# STM32H730_PINOUT.net
KiCad netlist of a schematic drawn in Altium Designer
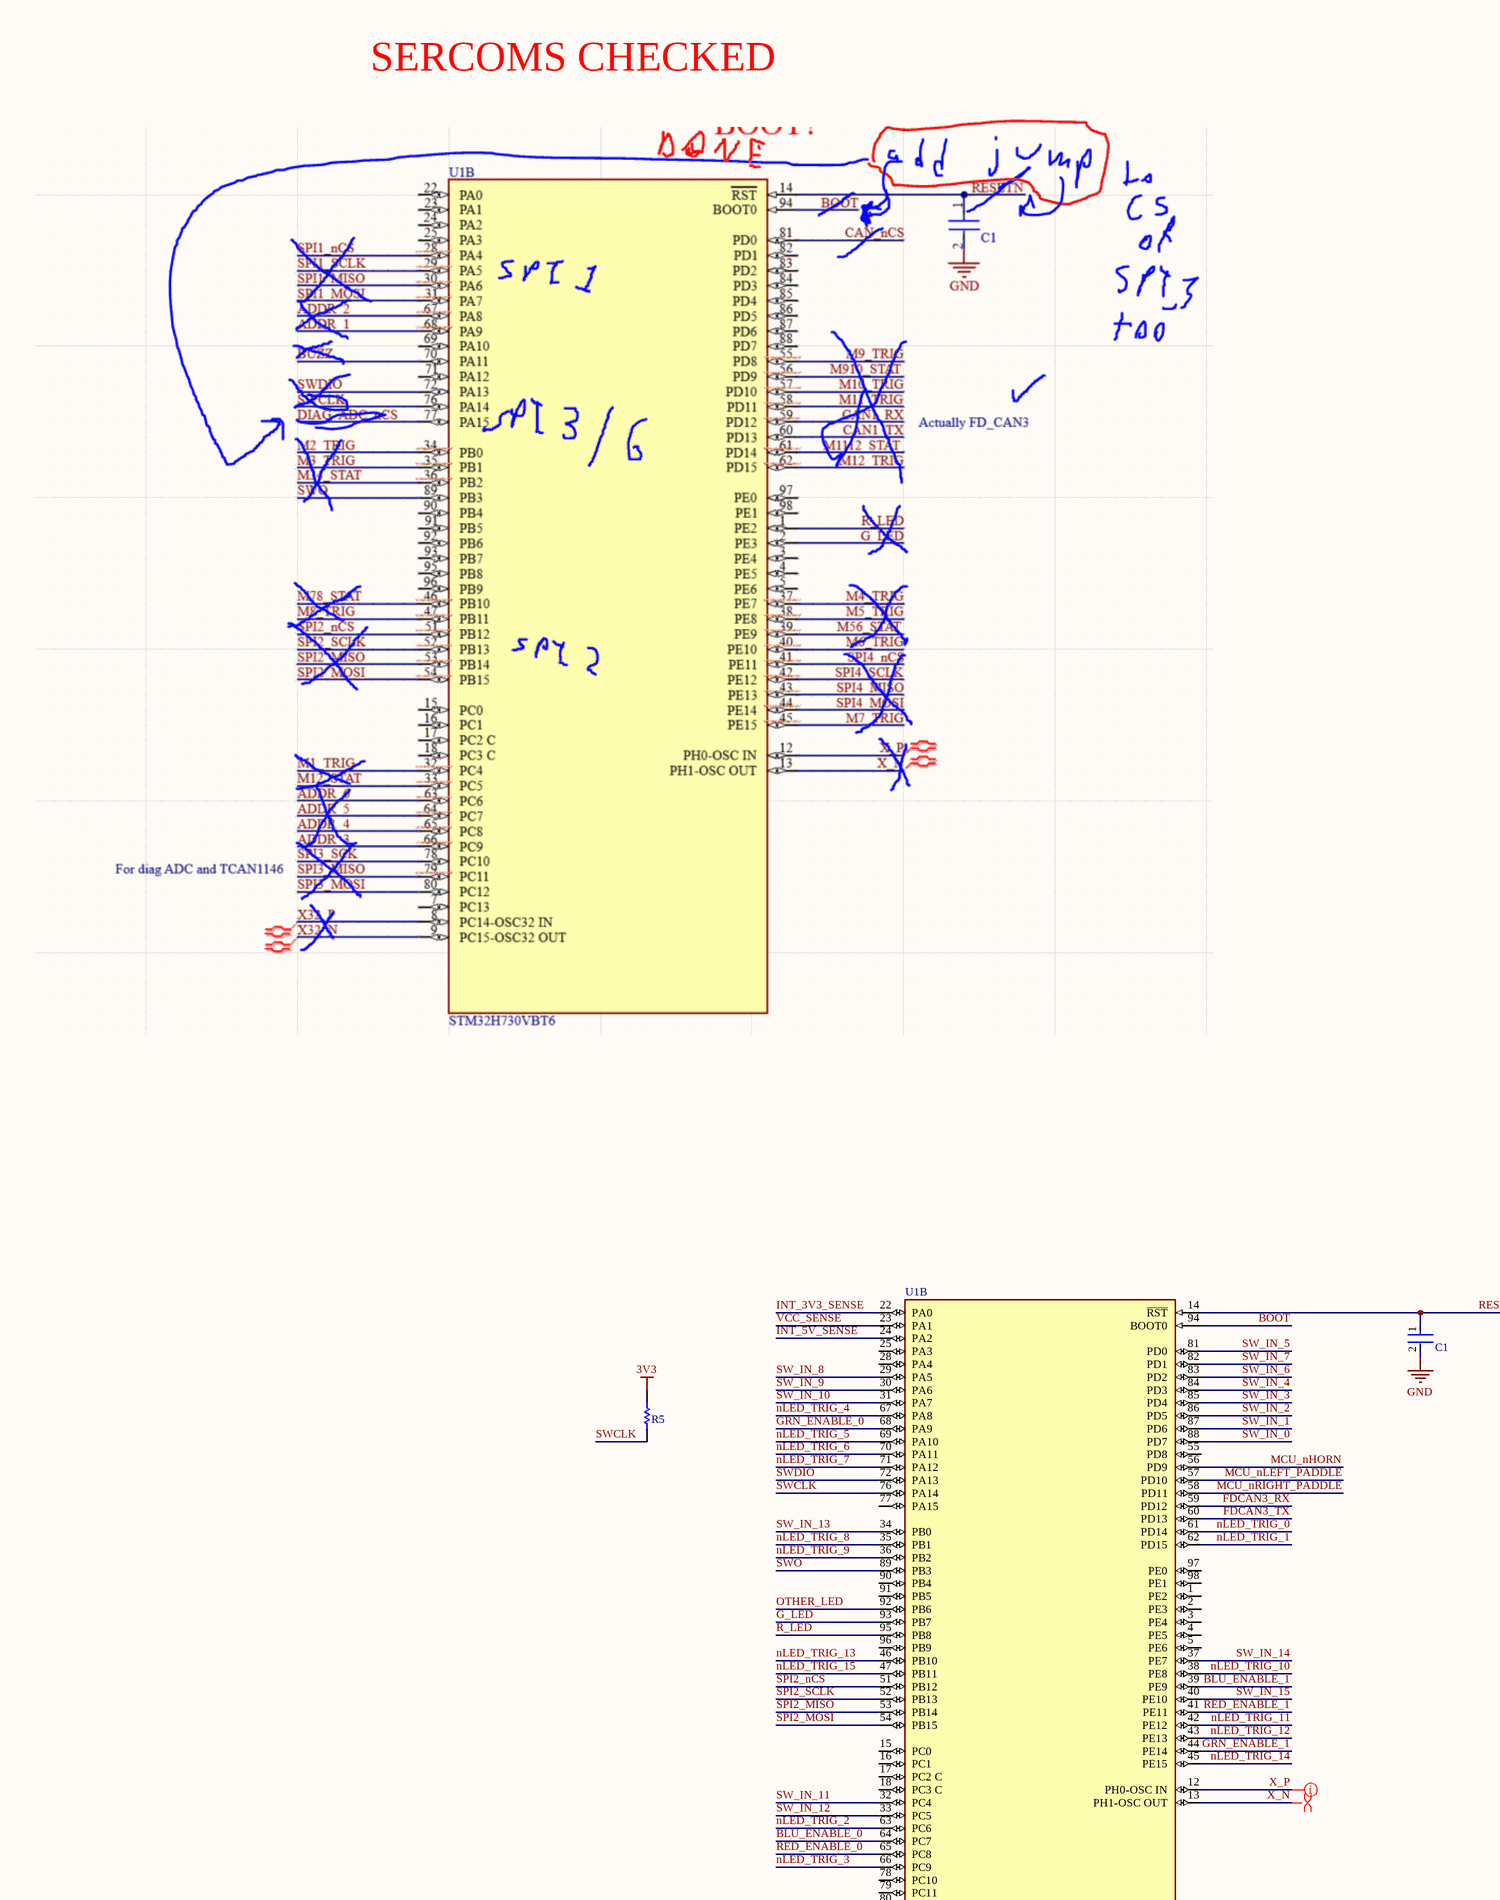
[diagram p0: STM32H730_PINOUT.SchDoc, top left]
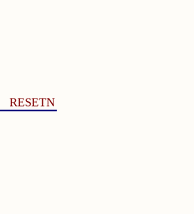
[diagram p1: STM32H730_PINOUT.SchDoc, top middle]
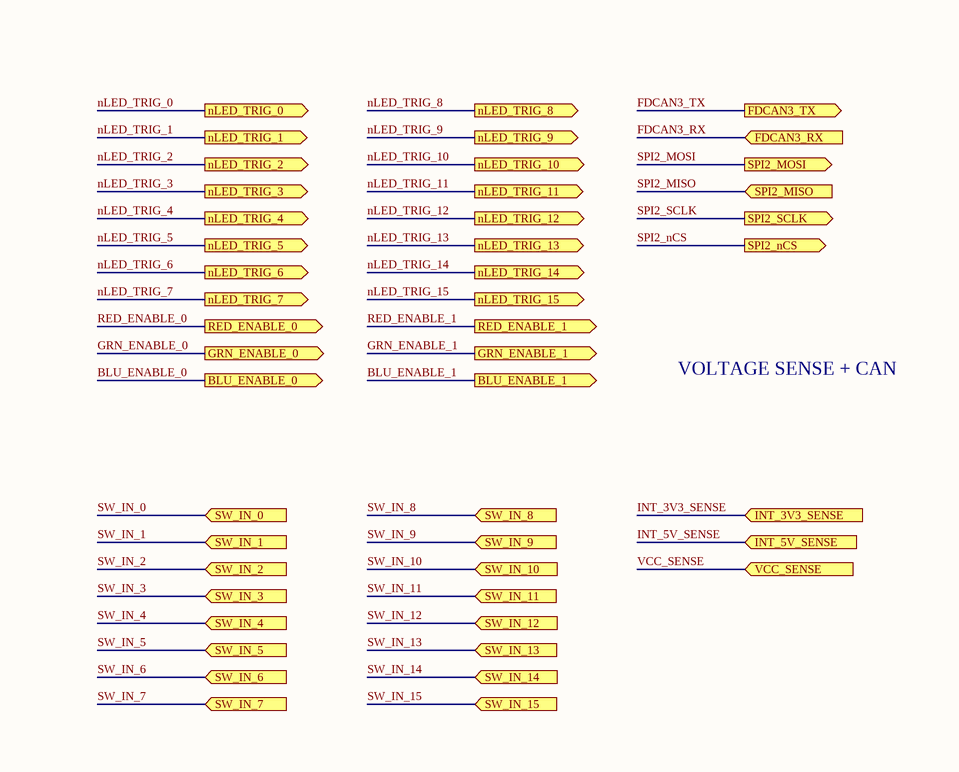
[diagram p2: STM32H730_PINOUT.SchDoc, top right]
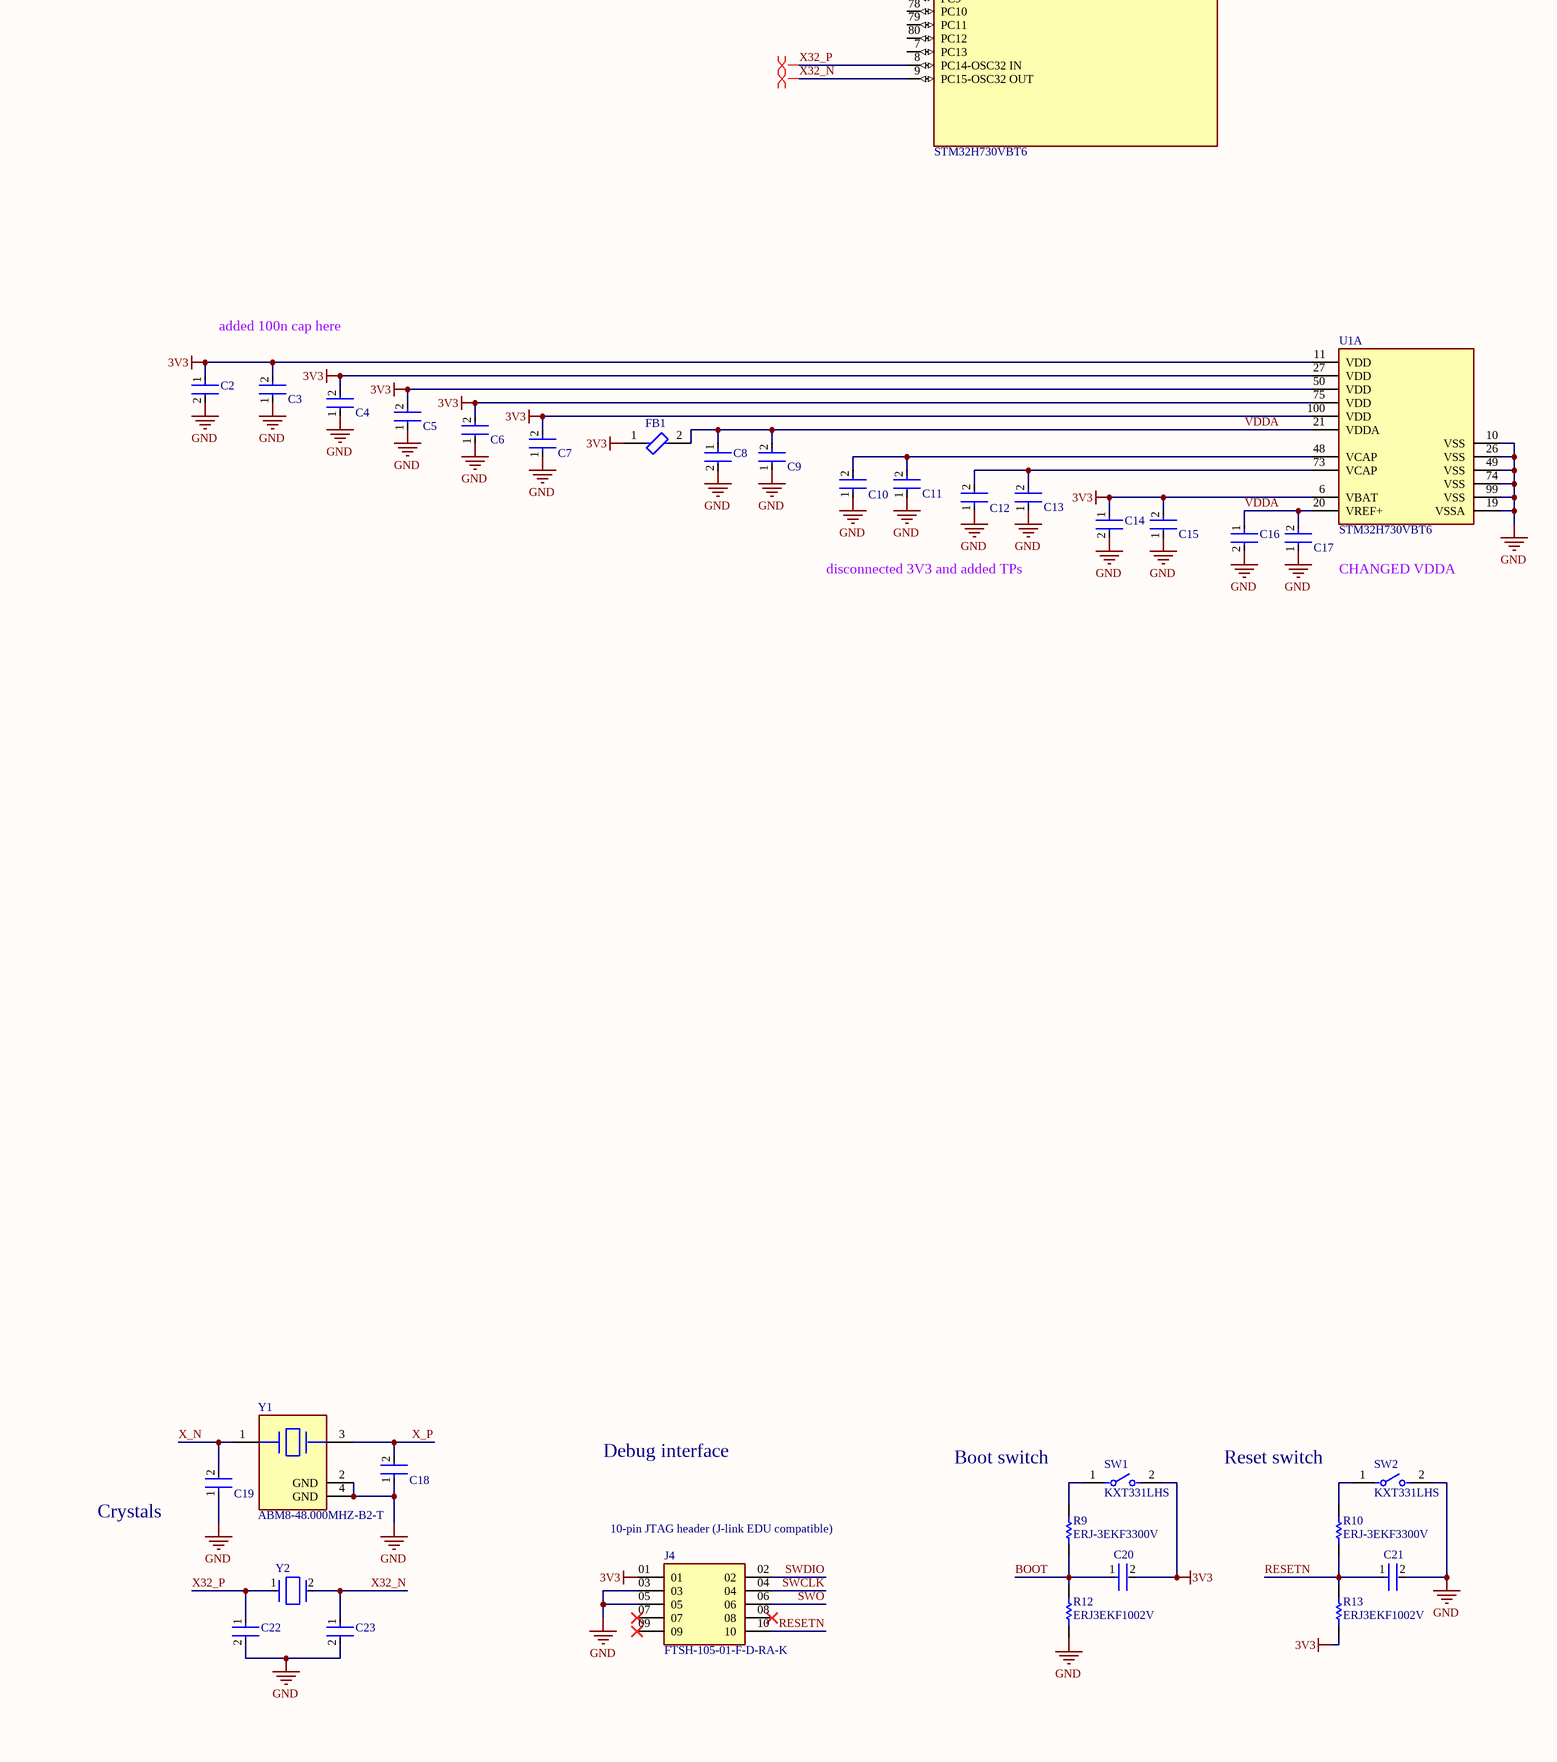
[diagram p3: STM32H730_PINOUT.SchDoc, bottom left]
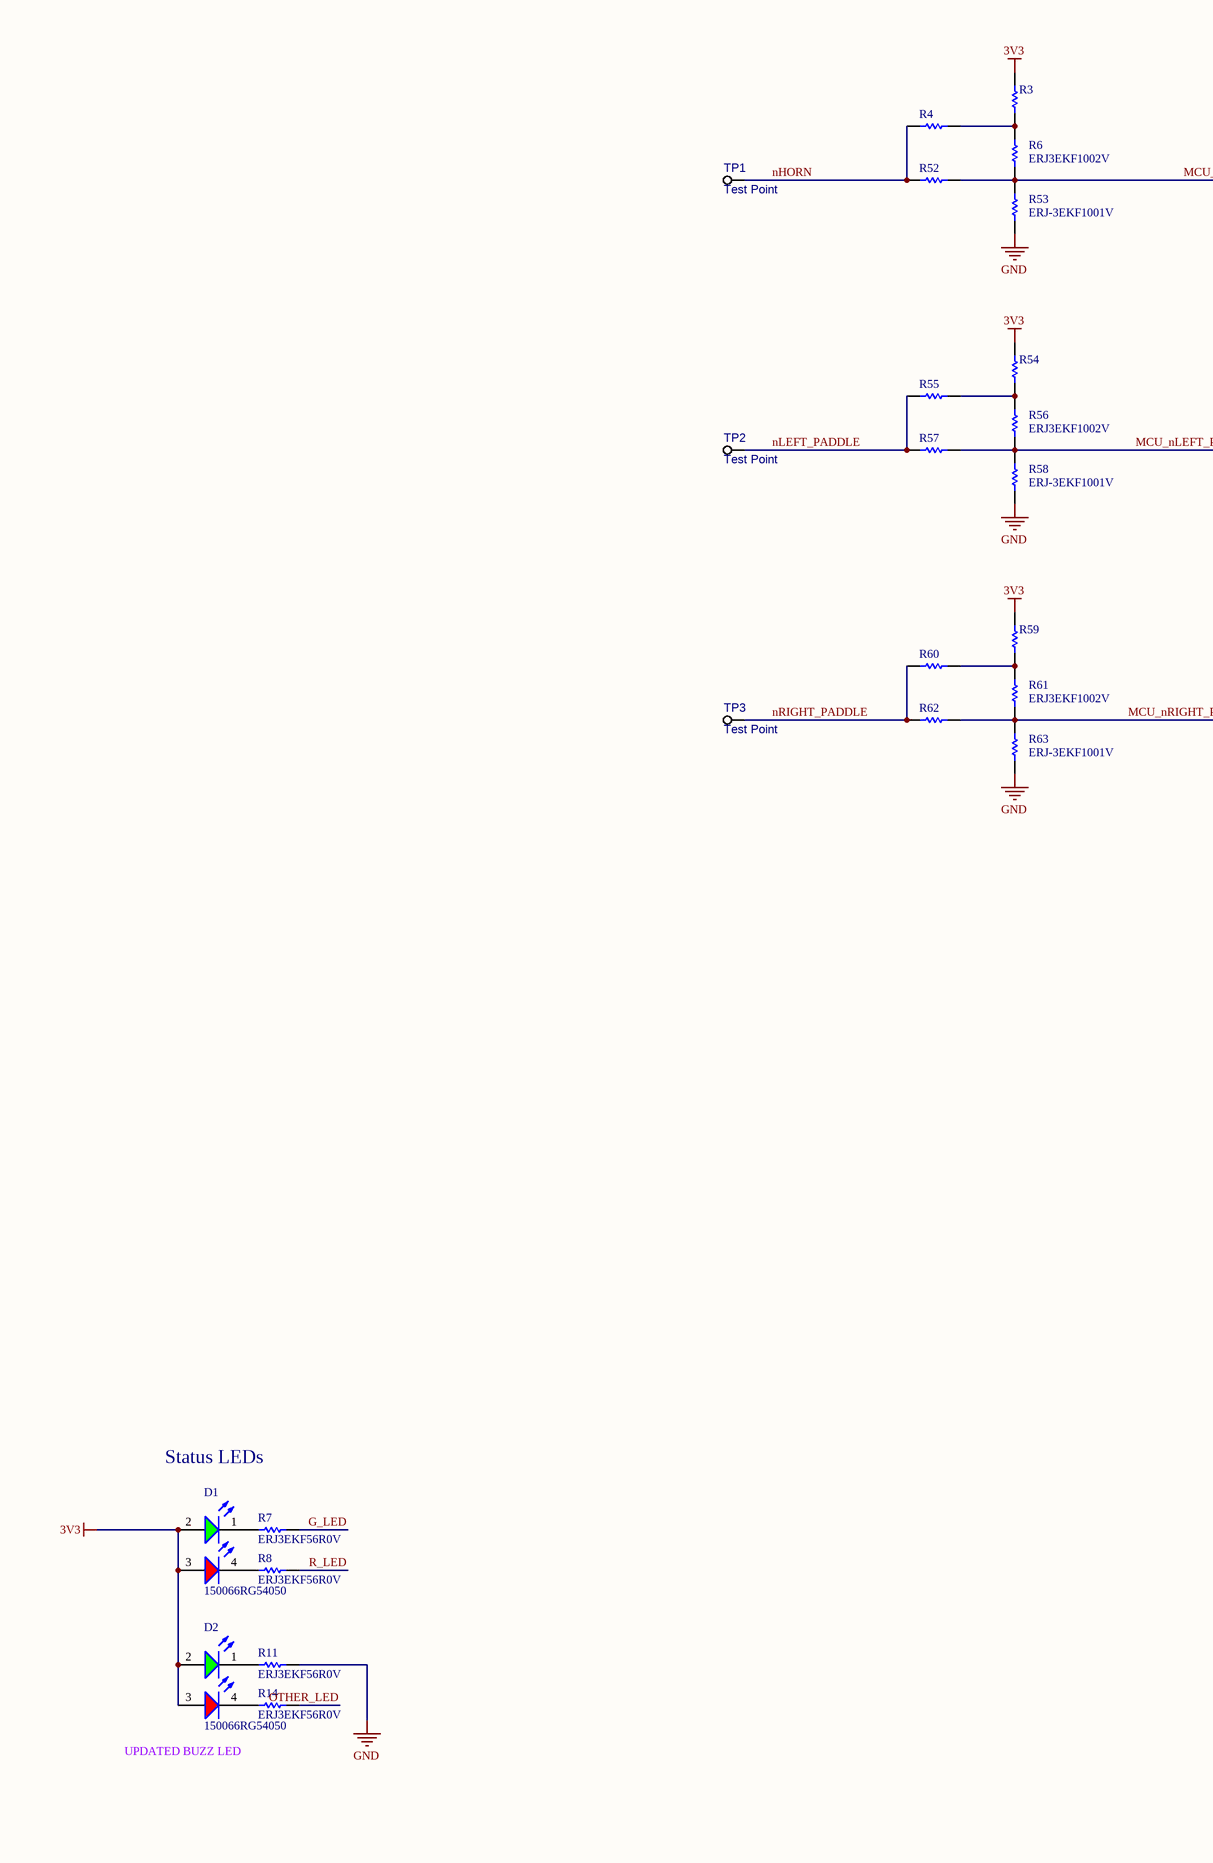
[diagram p4: STM32H730_PINOUT.SchDoc, bottom middle]
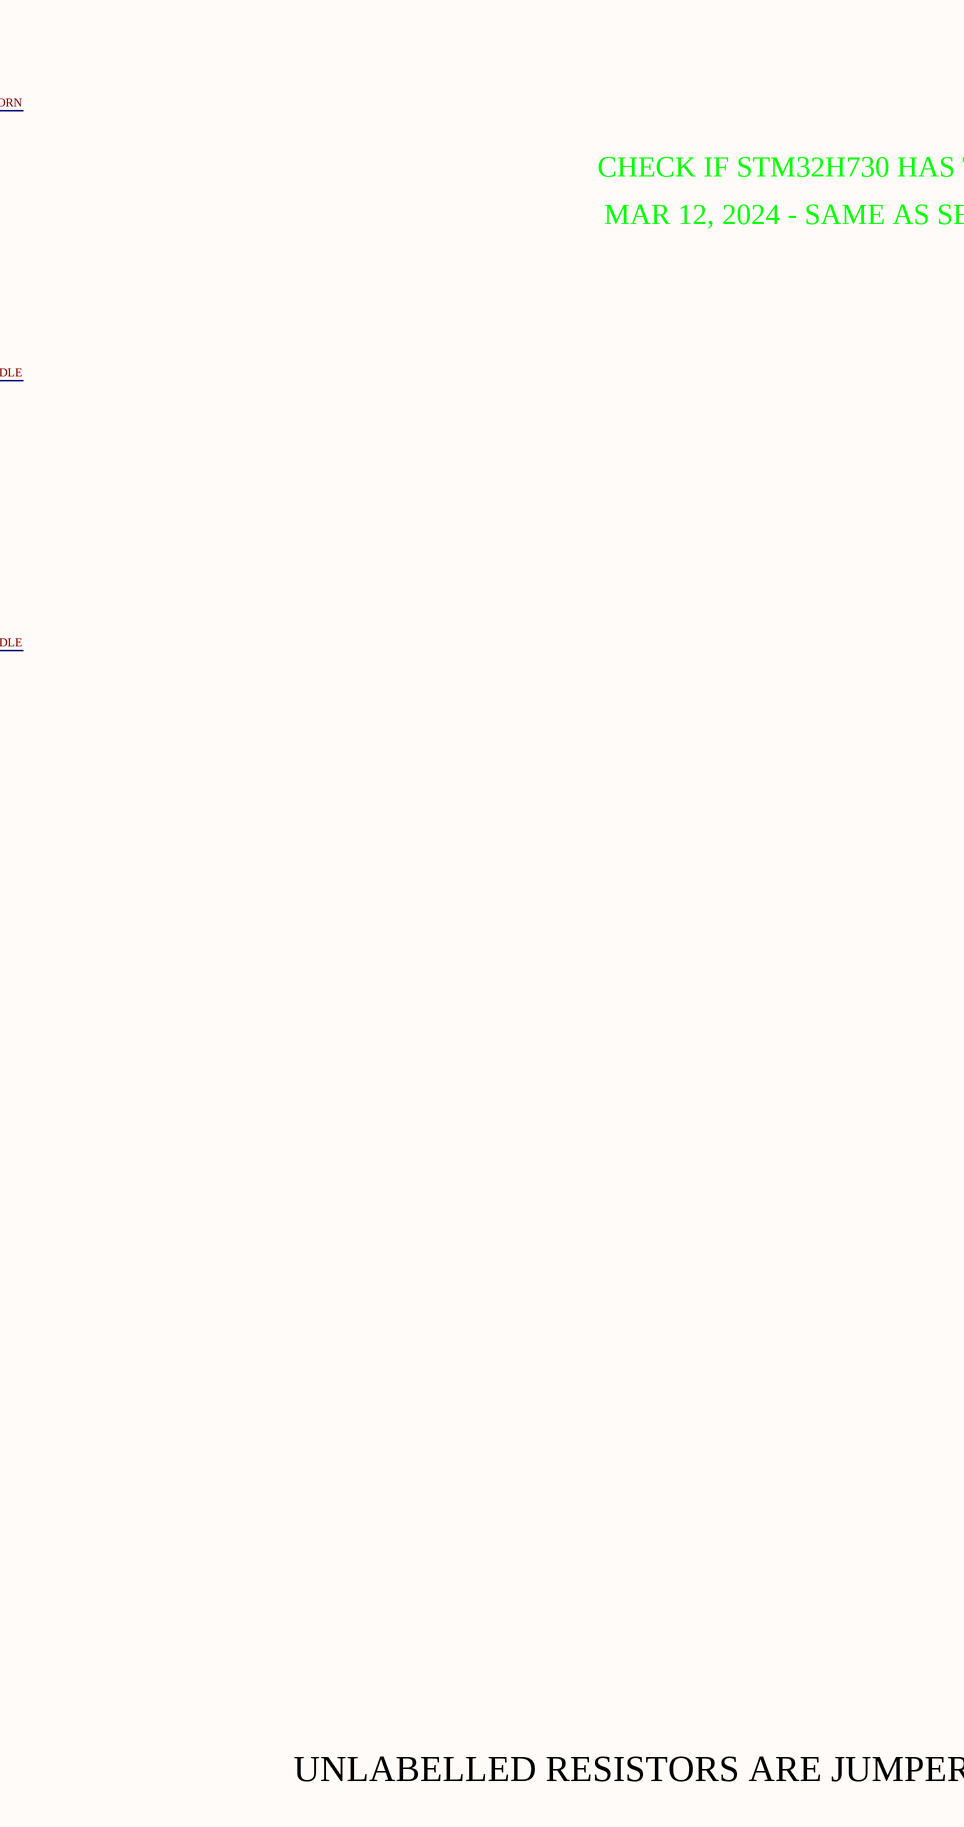
[diagram p5: STM32H730_PINOUT.SchDoc, bottom right]

(export (version "E")
  (design (tool "Eeschema 10.0.6"))
  (components
    (comp (ref "C1")
      (value "C0402C104K8PACTU")
      (footprint "FP-C0402-BB-MFG")
      (description "CAP CER 0.1UF 10V X5R 0402")
      (fields (field (name "MANUFACTURER") "Kemet") (field (name "TOLERANCE") "0.1"))
      (libsource (lib "Altium Content Vault") (part "b4654b650e69147ec39a6b967a45e02"))
    )
    (comp (ref "C2")
      (value "C1005X5R1A475K050BC")
      (footprint "FP-C1005-050-0_15-MFG")
      (description "CAP CER 4.7UF 10V X5R 0402")
      (fields (field (name "TOLERANCE") "10%"))
      (libsource (lib "Altium Content Vault") (part "b4654b650e69147ec39a6b967a45e02"))
    )
    (comp (ref "C3")
      (value "GRM155R71C104KA88D")
      (footprint "FP-GRM15-MFG")
      (description "CAP CER 0.1UF 16V X7R 0402")
      (fields
        (field (name "TOLERANCE") "10%")
        (field (name "OCTOPART") "https://octopart.com/grm155r71c104ka88d-murata-196880")
      )
      (libsource (lib "Altium Content Vault") (part "236180d848d6139a670b325ea6854c9"))
    )
    (comp (ref "C4")
      (value "GRM155R71C104KA88D")
      (footprint "FP-GRM15-MFG")
      (description "CAP CER 0.1UF 16V X7R 0402")
      (fields
        (field (name "TOLERANCE") "10%")
        (field (name "OCTOPART") "https://octopart.com/grm155r71c104ka88d-murata-196880")
      )
      (libsource (lib "Altium Content Vault") (part "236180d848d6139a670b325ea6854c9"))
    )
    (comp (ref "C5")
      (value "GRM155R71C104KA88D")
      (footprint "FP-GRM15-MFG")
      (description "CAP CER 0.1UF 16V X7R 0402")
      (fields
        (field (name "TOLERANCE") "10%")
        (field (name "OCTOPART") "https://octopart.com/grm155r71c104ka88d-murata-196880")
      )
      (libsource (lib "Altium Content Vault") (part "236180d848d6139a670b325ea6854c9"))
    )
    (comp (ref "C6")
      (value "GRM155R71C104KA88D")
      (footprint "FP-GRM15-MFG")
      (description "CAP CER 0.1UF 16V X7R 0402")
      (fields
        (field (name "TOLERANCE") "10%")
        (field (name "OCTOPART") "https://octopart.com/grm155r71c104ka88d-murata-196880")
      )
      (libsource (lib "Altium Content Vault") (part "236180d848d6139a670b325ea6854c9"))
    )
    (comp (ref "C7")
      (value "GRM155R71C104KA88D")
      (footprint "FP-GRM15-MFG")
      (description "CAP CER 0.1UF 16V X7R 0402")
      (fields
        (field (name "TOLERANCE") "10%")
        (field (name "OCTOPART") "https://octopart.com/grm155r71c104ka88d-murata-196880")
      )
      (libsource (lib "Altium Content Vault") (part "236180d848d6139a670b325ea6854c9"))
    )
    (comp (ref "C8")
      (value "EMK105BJ105KV-F")
      (footprint "FP-0402-L_1_0_0_05-W_0_5-IPC_A")
      (description "None")
      (fields (field (name "TOLERANCE") "10%"))
      (libsource (lib "Altium Content Vault") (part "b4654b650e69147ec39a6b967a45e02"))
    )
    (comp (ref "C9")
      (value "GRM155R71C104KA88D")
      (footprint "FP-GRM15-MFG")
      (description "CAP CER 0.1UF 16V X7R 0402")
      (fields
        (field (name "TOLERANCE") "10%")
        (field (name "OCTOPART") "https://octopart.com/grm155r71c104ka88d-murata-196880")
      )
      (libsource (lib "Altium Content Vault") (part "236180d848d6139a670b325ea6854c9"))
    )
    (comp (ref "C10")
      (value "C1005X7S1A225K050BC")
      (footprint "FP-C1005-050-0_15-0_1-MFG")
      (description "CAP CER 2.2UF 10V X7S 0402")
      (fields (field (name "TOLERANCE") "10%"))
      (libsource (lib "Altium Content Vault") (part "b4654b650e69147ec39a6b967a45e02"))
    )
    (comp (ref "C11")
      (value "GRM155R71C104KA88D")
      (footprint "FP-GRM15-MFG")
      (description "CAP CER 0.1UF 16V X7R 0402")
      (fields
        (field (name "TOLERANCE") "10%")
        (field (name "OCTOPART") "https://octopart.com/grm155r71c104ka88d-murata-196880")
      )
      (libsource (lib "Altium Content Vault") (part "236180d848d6139a670b325ea6854c9"))
    )
    (comp (ref "C12")
      (value "C1005X7S1A225K050BC")
      (footprint "FP-C1005-050-0_15-0_1-MFG")
      (description "CAP CER 2.2UF 10V X7S 0402")
      (fields (field (name "TOLERANCE") "10%"))
      (libsource (lib "Altium Content Vault") (part "b4654b650e69147ec39a6b967a45e02"))
    )
    (comp (ref "C13")
      (value "GRM155R71C104KA88D")
      (footprint "FP-GRM15-MFG")
      (description "CAP CER 0.1UF 16V X7R 0402")
      (fields
        (field (name "TOLERANCE") "10%")
        (field (name "OCTOPART") "https://octopart.com/grm155r71c104ka88d-murata-196880")
      )
      (libsource (lib "Altium Content Vault") (part "236180d848d6139a670b325ea6854c9"))
    )
    (comp (ref "C14")
      (value "EMK105BJ105KV-F")
      (footprint "FP-0402-L_1_0_0_05-W_0_5-IPC_A")
      (description "None")
      (fields (field (name "TOLERANCE") "10%"))
      (libsource (lib "Altium Content Vault") (part "b4654b650e69147ec39a6b967a45e02"))
    )
    (comp (ref "C15")
      (value "GRM155R71C104KA88D")
      (footprint "FP-GRM15-MFG")
      (description "CAP CER 0.1UF 16V X7R 0402")
      (fields
        (field (name "TOLERANCE") "10%")
        (field (name "OCTOPART") "https://octopart.com/grm155r71c104ka88d-murata-196880")
      )
      (libsource (lib "Altium Content Vault") (part "236180d848d6139a670b325ea6854c9"))
    )
    (comp (ref "C16")
      (value "EMK105BJ105KV-F")
      (footprint "FP-0402-L_1_0_0_05-W_0_5-IPC_A")
      (description "None")
      (fields (field (name "TOLERANCE") "10%"))
      (libsource (lib "Altium Content Vault") (part "b4654b650e69147ec39a6b967a45e02"))
    )
    (comp (ref "C17")
      (value "GRM155R71C104KA88D")
      (footprint "FP-GRM15-MFG")
      (description "CAP CER 0.1UF 16V X7R 0402")
      (fields
        (field (name "TOLERANCE") "10%")
        (field (name "OCTOPART") "https://octopart.com/grm155r71c104ka88d-murata-196880")
      )
      (libsource (lib "Altium Content Vault") (part "236180d848d6139a670b325ea6854c9"))
    )
    (comp (ref "C18")
      (value "08051A6R8CAT2A")
      (footprint "FP-0805-L_2_01_0_2-W_1_25-MFG")
      (description "General Purpose Ceramic Capacitor, 0805, 6.8pF, 0.25pF, C0G, 30ppm/°C, 100V")
      (fields (field (name "VOLTAGE") "100V") (field (name "TOLERANCE") "5%"))
      (libsource (lib "Altium Content Vault") (part "02cd4be3c70576c341d710602a673aa"))
    )
    (comp (ref "C19")
      (value "08051A6R8CAT2A")
      (footprint "FP-0805-L_2_01_0_2-W_1_25-MFG")
      (description "General Purpose Ceramic Capacitor, 0805, 6.8pF, 0.25pF, C0G, 30ppm/°C, 100V")
      (fields (field (name "VOLTAGE") "100V") (field (name "TOLERANCE") "5%"))
      (libsource (lib "Altium Content Vault") (part "02cd4be3c70576c341d710602a673aa"))
    )
    (comp (ref "C20")
      (value "C0402C104K8PACTU")
      (footprint "FP-C0402-BB-MFG")
      (description "CAP CER 0.1UF 10V X5R 0402")
      (fields (field (name "MANUFACTURER") "Kemet") (field (name "TOLERANCE") "0.1"))
      (libsource (lib "Altium Content Vault") (part "b4654b650e69147ec39a6b967a45e02"))
    )
    (comp (ref "C21")
      (value "C0402C104K8PACTU")
      (footprint "FP-C0402-BB-MFG")
      (description "CAP CER 0.1UF 10V X5R 0402")
      (fields (field (name "MANUFACTURER") "Kemet") (field (name "TOLERANCE") "0.1"))
      (libsource (lib "Altium Content Vault") (part "b4654b650e69147ec39a6b967a45e02"))
    )
    (comp (ref "C22")
      (value "04025A180FAT2A")
      (footprint "FP-0402-L_1_0_1-W_0_5_0_1-IPC_A")
      (description "General Purpose Ceramic Capacitor, 0402, 18pF, 1%, C0G, 30ppm/°C, 50V")
      (fields (field (name "TOLERANCE") "1%"))
      (libsource (lib "Altium Content Vault") (part "b4654b650e69147ec39a6b967a45e02"))
    )
    (comp (ref "C23")
      (value "04025A180FAT2A")
      (footprint "FP-0402-L_1_0_1-W_0_5_0_1-IPC_A")
      (description "General Purpose Ceramic Capacitor, 0402, 18pF, 1%, C0G, 30ppm/°C, 50V")
      (fields (field (name "TOLERANCE") "1%"))
      (libsource (lib "Altium Content Vault") (part "b4654b650e69147ec39a6b967a45e02"))
    )
    (comp (ref "D1")
      (value "150066RG54050")
      (footprint "WL-SBCD_0606")
      (description "Led, Red/Grn, 180Mcd/230Mcd, 624Nm/525Nm Rohs Compliant: Yes")
      (fields (field (name "SOURCE") "rgled.SchLib"))
      (libsource (lib "Space Concordia") (part "CMP-004-00034-2"))
    )
    (comp (ref "D2")
      (value "150066RG54050")
      (footprint "WL-SBCD_0606")
      (description "Led, Red/Grn, 180Mcd/230Mcd, 624Nm/525Nm Rohs Compliant: Yes")
      (fields (field (name "SOURCE") "rgled.SchLib"))
      (libsource (lib "Space Concordia") (part "CMP-004-00034-2"))
    )
    (comp (ref "FB1")
      (value "BLM15PX601SN1D")
      (footprint "FP-BLM15-0_05-MFG")
      (description "Chip Ferrite Bead, 0402, 600Ω @ 100MHz, 0.23Ω, 25%, 900mA")
      (fields (field (name "TOLERANCE") "25%"))
      (libsource (lib "Altium Content Vault") (part "5f30dd21d616792df468990f7003faa"))
    )
    (comp (ref "J4")
      (value "FTSH-105-01-F-D-RA-K")
      (footprint "FTSH-105-01-F-D-RA-K-Footprint-1")
      (libsource (lib "Space Concordia") (part "FTSH-105-01-F-D-RA-K-Symbol-1"))
    )
    (comp (ref "R3")
      (value "0402 JUMPER")
      (footprint "RESC1005X40X25ML05T05")
      (description "READ THE NAME")
      (libsource (lib "Space Concordia") (part "CMP-009-00206-2"))
    )
    (comp (ref "R4")
      (value "0402 JUMPER")
      (footprint "RESC1005X40X25ML05T05")
      (description "READ THE NAME")
      (libsource (lib "Space Concordia") (part "CMP-009-00206-2"))
    )
    (comp (ref "R5")
      (value "ERJ3EKF1002V")
      (footprint "RESC1609X55X30LL15T15")
      (description "Chip Resistor, 10 KOhm, +/- 1%, 0.1 W, -55 to 155 degC, 0603 (1608 Metric), RoHS, Tape and Reel")
      (fields (field (name "TOLERANCE") "1%") (field (name "MANUFACTURER") "Panasonic"))
      (libsource (lib "Altium Content Vault") (part "RES-2"))
    )
    (comp (ref "R6")
      (value "ERJ3EKF1002V")
      (footprint "RESC1609X55X30LL15T15")
      (description "Chip Resistor, 10 KOhm, +/- 1%, 0.1 W, -55 to 155 degC, 0603 (1608 Metric), RoHS, Tape and Reel")
      (fields (field (name "TOLERANCE") "1%") (field (name "MANUFACTURER") "Panasonic"))
      (libsource (lib "Altium Content Vault") (part "RES-2"))
    )
    (comp (ref "R7")
      (value "ERJ3EKF56R0V")
      (footprint "RESC1608X55X30NL15T15")
      (fields (field (name "MANUFACTURER") "Panasonic"))
      (libsource (lib "Altium Content Vault") (part "RES"))
    )
    (comp (ref "R8")
      (value "ERJ3EKF56R0V")
      (footprint "RESC1608X55X30NL15T15")
      (fields (field (name "MANUFACTURER") "Panasonic"))
      (libsource (lib "Altium Content Vault") (part "RES"))
    )
    (comp (ref "R9")
      (value "ERJ-3EKF3300V")
      (footprint "RESC1608X55X30LL15T15")
      (description "Chip Resistor, 330 Ohm, +/- 1%, 0.1 W, -55 to 155 degC, 0603 (1608 Metric), RoHS, Tape and Reel")
      (libsource (lib "Altium Content Vault") (part "RES-2"))
    )
    (comp (ref "R10")
      (value "ERJ-3EKF3300V")
      (footprint "RESC1608X55X30LL15T15")
      (description "Chip Resistor, 330 Ohm, +/- 1%, 0.1 W, -55 to 155 degC, 0603 (1608 Metric), RoHS, Tape and Reel")
      (libsource (lib "Altium Content Vault") (part "RES-2"))
    )
    (comp (ref "R11")
      (value "ERJ3EKF56R0V")
      (footprint "RESC1608X55X30NL15T15")
      (fields (field (name "MANUFACTURER") "Panasonic"))
      (libsource (lib "Altium Content Vault") (part "RES"))
    )
    (comp (ref "R12")
      (value "ERJ3EKF1002V")
      (footprint "RESC1609X55X30LL15T15")
      (description "Chip Resistor, 10 KOhm, +/- 1%, 0.1 W, -55 to 155 degC, 0603 (1608 Metric), RoHS, Tape and Reel")
      (fields (field (name "TOLERANCE") "1%") (field (name "MANUFACTURER") "Panasonic"))
      (libsource (lib "Altium Content Vault") (part "RES-2"))
    )
    (comp (ref "R13")
      (value "ERJ3EKF1002V")
      (footprint "RESC1609X55X30LL15T15")
      (description "Chip Resistor, 10 KOhm, +/- 1%, 0.1 W, -55 to 155 degC, 0603 (1608 Metric), RoHS, Tape and Reel")
      (fields (field (name "TOLERANCE") "1%") (field (name "MANUFACTURER") "Panasonic"))
      (libsource (lib "Altium Content Vault") (part "RES-2"))
    )
    (comp (ref "R14")
      (value "ERJ3EKF56R0V")
      (footprint "RESC1608X55X30NL15T15")
      (fields (field (name "MANUFACTURER") "Panasonic"))
      (libsource (lib "Altium Content Vault") (part "RES"))
    )
    (comp (ref "R52")
      (value "0402 JUMPER")
      (footprint "RESC1005X40X25ML05T05")
      (description "READ THE NAME")
      (libsource (lib "Space Concordia") (part "CMP-009-00206-2"))
    )
    (comp (ref "R53")
      (value "ERJ-3EKF1001V")
      (footprint "RESC1608X55X30LL15T15")
      (fields (field (name "MANUFACTURER") "Panasonic"))
      (libsource (lib "Altium Content Vault") (part "RES"))
    )
    (comp (ref "R54")
      (value "0402 JUMPER")
      (footprint "RESC1005X40X25ML05T05")
      (description "READ THE NAME")
      (libsource (lib "Space Concordia") (part "CMP-009-00206-2"))
    )
    (comp (ref "R55")
      (value "0402 JUMPER")
      (footprint "RESC1005X40X25ML05T05")
      (description "READ THE NAME")
      (libsource (lib "Space Concordia") (part "CMP-009-00206-2"))
    )
    (comp (ref "R56")
      (value "ERJ3EKF1002V")
      (footprint "RESC1609X55X30LL15T15")
      (description "Chip Resistor, 10 KOhm, +/- 1%, 0.1 W, -55 to 155 degC, 0603 (1608 Metric), RoHS, Tape and Reel")
      (fields (field (name "TOLERANCE") "1%") (field (name "MANUFACTURER") "Panasonic"))
      (libsource (lib "Altium Content Vault") (part "RES-2"))
    )
    (comp (ref "R57")
      (value "0402 JUMPER")
      (footprint "RESC1005X40X25ML05T05")
      (description "READ THE NAME")
      (libsource (lib "Space Concordia") (part "CMP-009-00206-2"))
    )
    (comp (ref "R58")
      (value "ERJ-3EKF1001V")
      (footprint "RESC1608X55X30LL15T15")
      (fields (field (name "MANUFACTURER") "Panasonic"))
      (libsource (lib "Altium Content Vault") (part "RES"))
    )
    (comp (ref "R59")
      (value "0402 JUMPER")
      (footprint "RESC1005X40X25ML05T05")
      (description "READ THE NAME")
      (libsource (lib "Space Concordia") (part "CMP-009-00206-2"))
    )
    (comp (ref "R60")
      (value "0402 JUMPER")
      (footprint "RESC1005X40X25ML05T05")
      (description "READ THE NAME")
      (libsource (lib "Space Concordia") (part "CMP-009-00206-2"))
    )
    (comp (ref "R61")
      (value "ERJ3EKF1002V")
      (footprint "RESC1609X55X30LL15T15")
      (description "Chip Resistor, 10 KOhm, +/- 1%, 0.1 W, -55 to 155 degC, 0603 (1608 Metric), RoHS, Tape and Reel")
      (fields (field (name "TOLERANCE") "1%") (field (name "MANUFACTURER") "Panasonic"))
      (libsource (lib "Altium Content Vault") (part "RES-2"))
    )
    (comp (ref "R62")
      (value "0402 JUMPER")
      (footprint "RESC1005X40X25ML05T05")
      (description "READ THE NAME")
      (libsource (lib "Space Concordia") (part "CMP-009-00206-2"))
    )
    (comp (ref "R63")
      (value "ERJ-3EKF1001V")
      (footprint "RESC1608X55X30LL15T15")
      (fields (field (name "MANUFACTURER") "Panasonic"))
      (libsource (lib "Altium Content Vault") (part "RES"))
    )
    (comp (ref "SW1")
      (value "KXT331LHS")
      (footprint "FP-KXT331LHS-MFG")
      (description "SWITCH TACTILE SPST-NO 0.02A 15V")
      (libsource (lib "Altium Content Vault") (part "bb27bde45df87f1f469753f287ef5ae"))
    )
    (comp (ref "SW2")
      (value "KXT331LHS")
      (footprint "FP-KXT331LHS-MFG")
      (description "SWITCH TACTILE SPST-NO 0.02A 15V")
      (libsource (lib "Altium Content Vault") (part "bb27bde45df87f1f469753f287ef5ae"))
    )
    (comp (ref "TP1")
      (value "Test Point")
      (footprint "TP-SMT-1mm")
      (description "In circuit test point for a net")
      (libsource (lib "Space Concordia") (part "Test Point"))
    )
    (comp (ref "TP2")
      (value "Test Point")
      (footprint "TP-SMT-1mm")
      (description "In circuit test point for a net")
      (libsource (lib "Space Concordia") (part "Test Point"))
    )
    (comp (ref "TP3")
      (value "Test Point")
      (footprint "TP-SMT-1mm")
      (description "In circuit test point for a net")
      (libsource (lib "Space Concordia") (part "Test Point"))
    )
    (comp (ref "U1")
      (value "STM32H730VBT6")
      (footprint "FP-LQFP100-1L-IPC_C")
      (description "IC MCU 32BIT 128KB FLASH 100LQFP")
      (libsource (lib "Altium Content Vault") (part "44dc6501260a4d92b846760feb66c20"))
    )
    (comp (ref "Y1")
      (value "ABM8-48.000MHZ-B2-T")
      (footprint "FP-ABM8-MFG")
      (description "Crystal 48MHz ±20ppm 18pF SMD-4 3.2mm x 2.5mm")
      (fields (field (name "TOLERANCE") "20ppm"))
      (libsource (lib "Altium Content Vault") (part "dfdb7f9a12507849fb681da9a70121c"))
    )
    (comp (ref "Y2")
      (value "ECS-.327-12.5-1210-TR")
      (footprint "FP-ECX-1210-MFG")
      (description "CRYSTAL 32.7680KHZ 12.5PF SMD")
      (fields
        (field (name "OCTOPART") "https://octopart.com/ecs-.327-12.5-1210-tr-ecs+international-81221340")
        (field (name "TOLERANCE") "20ppm")
      )
      (libsource (lib "Altium Content Vault") (part "99724985039315a44fd0d1401b84e49"))
    )
  )
  (nets
    (net (code "1") (name "/BLU_ENABLE_0") (class "Default")
      (node (ref "U1") (pin "64") (pinfunction "PC7_64") (pintype "bidirectional"))
    )
    (net (code "2") (name "/BLU_ENABLE_1") (class "Default")
      (node (ref "U1") (pin "39") (pinfunction "PE9_39") (pintype "bidirectional"))
    )
    (net (code "3") (name "/BOOT") (class "Default")
      (node (ref "C20") (pin "1") (pinfunction "1_1") (pintype "passive"))
      (node (ref "R12") (pin "2") (pinfunction "2_2") (pintype "passive"))
      (node (ref "R9") (pin "1") (pinfunction "1_1") (pintype "passive"))
      (node (ref "U1") (pin "94") (pinfunction "BOOT0_94") (pintype "input"))
    )
    (net (code "4") (name "/FDCAN3_RX") (class "Default")
      (node (ref "U1") (pin "59") (pinfunction "PD12_59") (pintype "bidirectional"))
    )
    (net (code "5") (name "/FDCAN3_TX") (class "Default")
      (node (ref "U1") (pin "60") (pinfunction "PD13_60") (pintype "bidirectional"))
    )
    (net (code "6") (name "/GRN_ENABLE_0") (class "Default")
      (node (ref "U1") (pin "68") (pinfunction "PA9_68") (pintype "bidirectional"))
    )
    (net (code "7") (name "/GRN_ENABLE_1") (class "Default")
      (node (ref "U1") (pin "44") (pinfunction "PE14_44") (pintype "bidirectional"))
    )
    (net (code "8") (name "/G_LED") (class "Default")
      (node (ref "R7") (pin "1") (pinfunction "1_1") (pintype "passive"))
      (node (ref "U1") (pin "93") (pinfunction "PB7_93") (pintype "bidirectional"))
    )
    (net (code "9") (name "/INT_3V3_SENSE") (class "Default")
      (node (ref "U1") (pin "22") (pinfunction "PA0_22") (pintype "bidirectional"))
    )
    (net (code "10") (name "/INT_5V_SENSE") (class "Default")
      (node (ref "U1") (pin "24") (pinfunction "PA2_24") (pintype "bidirectional"))
    )
    (net (code "11") (name "/MCU_nHORN") (class "Default")
      (node (ref "R52") (pin "2") (pinfunction "2_2") (pintype "passive"))
      (node (ref "R53") (pin "2") (pinfunction "2_2") (pintype "passive"))
      (node (ref "R6") (pin "2") (pinfunction "2_2") (pintype "passive"))
      (node (ref "U1") (pin "56") (pinfunction "PD9_56") (pintype "bidirectional"))
    )
    (net (code "12") (name "/MCU_nLEFT_PADDLE") (class "Default")
      (node (ref "R56") (pin "2") (pinfunction "2_2") (pintype "passive"))
      (node (ref "R57") (pin "2") (pinfunction "2_2") (pintype "passive"))
      (node (ref "R58") (pin "2") (pinfunction "2_2") (pintype "passive"))
      (node (ref "U1") (pin "57") (pinfunction "PD10_57") (pintype "bidirectional"))
    )
    (net (code "13") (name "/MCU_nRIGHT_PADDLE") (class "Default")
      (node (ref "R61") (pin "2") (pinfunction "2_2") (pintype "passive"))
      (node (ref "R62") (pin "2") (pinfunction "2_2") (pintype "passive"))
      (node (ref "R63") (pin "2") (pinfunction "2_2") (pintype "passive"))
      (node (ref "U1") (pin "58") (pinfunction "PD11_58") (pintype "bidirectional"))
    )
    (net (code "14") (name "/OTHER_LED") (class "Default")
      (node (ref "R14") (pin "1") (pinfunction "1_1") (pintype "passive"))
      (node (ref "U1") (pin "92") (pinfunction "PB6_92") (pintype "bidirectional"))
    )
    (net (code "15") (name "/RED_ENABLE_0") (class "Default")
      (node (ref "U1") (pin "65") (pinfunction "PC8_65") (pintype "bidirectional"))
    )
    (net (code "16") (name "/RED_ENABLE_1") (class "Default")
      (node (ref "U1") (pin "41") (pinfunction "PE11_41") (pintype "bidirectional"))
    )
    (net (code "17") (name "/RESETN") (class "Default")
      (node (ref "C1") (pin "1") (pinfunction "1_1") (pintype "passive"))
      (node (ref "C21") (pin "1") (pinfunction "1_1") (pintype "passive"))
      (node (ref "J4") (pin "10") (pinfunction "10_10") (pintype "passive"))
      (node (ref "R10") (pin "1") (pinfunction "1_1") (pintype "passive"))
      (node (ref "R13") (pin "2") (pinfunction "2_2") (pintype "passive"))
      (node (ref "U1") (pin "14") (pinfunction "~{RST}_14") (pintype "input"))
    )
    (net (code "18") (name "/R_LED") (class "Default")
      (node (ref "R8") (pin "1") (pinfunction "1_1") (pintype "passive"))
      (node (ref "U1") (pin "95") (pinfunction "PB8_95") (pintype "bidirectional"))
    )
    (net (code "19") (name "/SPI2_MISO") (class "Default")
      (node (ref "U1") (pin "53") (pinfunction "PB14_53") (pintype "bidirectional"))
    )
    (net (code "20") (name "/SPI2_MOSI") (class "Default")
      (node (ref "U1") (pin "54") (pinfunction "PB15_54") (pintype "bidirectional"))
    )
    (net (code "21") (name "/SPI2_SCLK") (class "Default")
      (node (ref "U1") (pin "52") (pinfunction "PB13_52") (pintype "bidirectional"))
    )
    (net (code "22") (name "/SPI2_nCS") (class "Default")
      (node (ref "U1") (pin "51") (pinfunction "PB12_51") (pintype "bidirectional"))
    )
    (net (code "23") (name "/SWCLK") (class "Default")
      (node (ref "J4") (pin "04") (pinfunction "04_04") (pintype "passive"))
      (node (ref "R5") (pin "2") (pinfunction "2_2") (pintype "passive"))
      (node (ref "U1") (pin "76") (pinfunction "PA14_76") (pintype "bidirectional"))
    )
    (net (code "24") (name "/SWDIO") (class "Default")
      (node (ref "J4") (pin "02") (pinfunction "02_02") (pintype "passive"))
      (node (ref "U1") (pin "72") (pinfunction "PA13_72") (pintype "bidirectional"))
    )
    (net (code "25") (name "/SWO") (class "Default")
      (node (ref "J4") (pin "06") (pinfunction "06_06") (pintype "passive"))
      (node (ref "U1") (pin "89") (pinfunction "PB3_89") (pintype "bidirectional"))
    )
    (net (code "26") (name "/SW_IN_0") (class "Default")
      (node (ref "U1") (pin "88") (pinfunction "PD7_88") (pintype "bidirectional"))
    )
    (net (code "27") (name "/SW_IN_1") (class "Default")
      (node (ref "U1") (pin "87") (pinfunction "PD6_87") (pintype "bidirectional"))
    )
    (net (code "28") (name "/SW_IN_2") (class "Default")
      (node (ref "U1") (pin "86") (pinfunction "PD5_86") (pintype "bidirectional"))
    )
    (net (code "29") (name "/SW_IN_3") (class "Default")
      (node (ref "U1") (pin "85") (pinfunction "PD4_85") (pintype "bidirectional"))
    )
    (net (code "30") (name "/SW_IN_4") (class "Default")
      (node (ref "U1") (pin "84") (pinfunction "PD3_84") (pintype "bidirectional"))
    )
    (net (code "31") (name "/SW_IN_5") (class "Default")
      (node (ref "U1") (pin "81") (pinfunction "PD0_81") (pintype "bidirectional"))
    )
    (net (code "32") (name "/SW_IN_6") (class "Default")
      (node (ref "U1") (pin "83") (pinfunction "PD2_83") (pintype "bidirectional"))
    )
    (net (code "33") (name "/SW_IN_7") (class "Default")
      (node (ref "U1") (pin "82") (pinfunction "PD1_82") (pintype "bidirectional"))
    )
    (net (code "34") (name "/SW_IN_8") (class "Default")
      (node (ref "U1") (pin "29") (pinfunction "PA5_29") (pintype "bidirectional"))
    )
    (net (code "35") (name "/SW_IN_9") (class "Default")
      (node (ref "U1") (pin "30") (pinfunction "PA6_30") (pintype "bidirectional"))
    )
    (net (code "36") (name "/SW_IN_10") (class "Default")
      (node (ref "U1") (pin "31") (pinfunction "PA7_31") (pintype "bidirectional"))
    )
    (net (code "37") (name "/SW_IN_11") (class "Default")
      (node (ref "U1") (pin "32") (pinfunction "PC4_32") (pintype "bidirectional"))
    )
    (net (code "38") (name "/SW_IN_12") (class "Default")
      (node (ref "U1") (pin "33") (pinfunction "PC5_33") (pintype "bidirectional"))
    )
    (net (code "39") (name "/SW_IN_13") (class "Default")
      (node (ref "U1") (pin "34") (pinfunction "PB0_34") (pintype "bidirectional"))
    )
    (net (code "40") (name "/SW_IN_14") (class "Default")
      (node (ref "U1") (pin "37") (pinfunction "PE7_37") (pintype "bidirectional"))
    )
    (net (code "41") (name "/SW_IN_15") (class "Default")
      (node (ref "U1") (pin "40") (pinfunction "PE10_40") (pintype "bidirectional"))
    )
    (net (code "42") (name "/VCC_SENSE") (class "Default")
      (node (ref "U1") (pin "23") (pinfunction "PA1_23") (pintype "bidirectional"))
    )
    (net (code "43") (name "/VDDA") (class "Default")
      (node (ref "C16") (pin "1") (pinfunction "1_1") (pintype "passive"))
      (node (ref "C17") (pin "2") (pinfunction "2_2") (pintype "passive"))
      (node (ref "C8") (pin "1") (pinfunction "1_1") (pintype "passive"))
      (node (ref "C9") (pin "2") (pinfunction "2_2") (pintype "passive"))
      (node (ref "FB1") (pin "2") (pinfunction "2_2") (pintype "passive"))
      (node (ref "U1") (pin "20") (pinfunction "VREF+_20") (pintype "power_in"))
      (node (ref "U1") (pin "21") (pinfunction "VDDA_21") (pintype "power_in"))
    )
    (net (code "44") (name "/X32_N") (class "Default")
      (node (ref "C23") (pin "1") (pinfunction "1_1") (pintype "passive"))
      (node (ref "U1") (pin "9") (pinfunction "PC15-OSC32_OUT_9") (pintype "bidirectional"))
      (node (ref "Y2") (pin "2") (pinfunction "Out/In_2") (pintype "passive"))
    )
    (net (code "45") (name "/X32_P") (class "Default")
      (node (ref "C22") (pin "1") (pinfunction "1_1") (pintype "passive"))
      (node (ref "U1") (pin "8") (pinfunction "PC14-OSC32_IN_8") (pintype "bidirectional"))
      (node (ref "Y2") (pin "1") (pinfunction "In/Out_1") (pintype "passive"))
    )
    (net (code "46") (name "/X_N") (class "Default")
      (node (ref "C19") (pin "2") (pinfunction "2_2") (pintype "passive"))
      (node (ref "U1") (pin "13") (pinfunction "PH1-OSC_OUT_13") (pintype "bidirectional"))
      (node (ref "Y1") (pin "1") (pinfunction "1_1") (pintype "passive"))
    )
    (net (code "47") (name "/X_P") (class "Default")
      (node (ref "C18") (pin "2") (pinfunction "2_2") (pintype "passive"))
      (node (ref "U1") (pin "12") (pinfunction "PH0-OSC_IN_12") (pintype "bidirectional"))
      (node (ref "Y1") (pin "3") (pinfunction "3_3") (pintype "passive"))
    )
    (net (code "48") (name "/nHORN") (class "Default")
      (node (ref "R4") (pin "1") (pinfunction "1_1") (pintype "passive"))
      (node (ref "R52") (pin "1") (pinfunction "1_1") (pintype "passive"))
      (node (ref "TP1") (pin "1") (pinfunction "Pad_1") (pintype "passive"))
    )
    (net (code "49") (name "/nLED_TRIG_0") (class "Default")
      (node (ref "U1") (pin "61") (pinfunction "PD14_61") (pintype "bidirectional"))
    )
    (net (code "50") (name "/nLED_TRIG_1") (class "Default")
      (node (ref "U1") (pin "62") (pinfunction "PD15_62") (pintype "bidirectional"))
    )
    (net (code "51") (name "/nLED_TRIG_2") (class "Default")
      (node (ref "U1") (pin "63") (pinfunction "PC6_63") (pintype "bidirectional"))
    )
    (net (code "52") (name "/nLED_TRIG_3") (class "Default")
      (node (ref "U1") (pin "66") (pinfunction "PC9_66") (pintype "bidirectional"))
    )
    (net (code "53") (name "/nLED_TRIG_4") (class "Default")
      (node (ref "U1") (pin "67") (pinfunction "PA8_67") (pintype "bidirectional"))
    )
    (net (code "54") (name "/nLED_TRIG_5") (class "Default")
      (node (ref "U1") (pin "69") (pinfunction "PA10_69") (pintype "bidirectional"))
    )
    (net (code "55") (name "/nLED_TRIG_6") (class "Default")
      (node (ref "U1") (pin "70") (pinfunction "PA11_70") (pintype "bidirectional"))
    )
    (net (code "56") (name "/nLED_TRIG_7") (class "Default")
      (node (ref "U1") (pin "71") (pinfunction "PA12_71") (pintype "bidirectional"))
    )
    (net (code "57") (name "/nLED_TRIG_8") (class "Default")
      (node (ref "U1") (pin "35") (pinfunction "PB1_35") (pintype "bidirectional"))
    )
    (net (code "58") (name "/nLED_TRIG_9") (class "Default")
      (node (ref "U1") (pin "36") (pinfunction "PB2_36") (pintype "bidirectional"))
    )
    (net (code "59") (name "/nLED_TRIG_10") (class "Default")
      (node (ref "U1") (pin "38") (pinfunction "PE8_38") (pintype "bidirectional"))
    )
    (net (code "60") (name "/nLED_TRIG_11") (class "Default")
      (node (ref "U1") (pin "42") (pinfunction "PE12_42") (pintype "bidirectional"))
    )
    (net (code "61") (name "/nLED_TRIG_12") (class "Default")
      (node (ref "U1") (pin "43") (pinfunction "PE13_43") (pintype "bidirectional"))
    )
    (net (code "62") (name "/nLED_TRIG_13") (class "Default")
      (node (ref "U1") (pin "46") (pinfunction "PB10_46") (pintype "bidirectional"))
    )
    (net (code "63") (name "/nLED_TRIG_14") (class "Default")
      (node (ref "U1") (pin "45") (pinfunction "PE15_45") (pintype "bidirectional"))
    )
    (net (code "64") (name "/nLED_TRIG_15") (class "Default")
      (node (ref "U1") (pin "47") (pinfunction "PB11_47") (pintype "bidirectional"))
    )
    (net (code "65") (name "/nLEFT_PADDLE") (class "Default")
      (node (ref "R55") (pin "1") (pinfunction "1_1") (pintype "passive"))
      (node (ref "R57") (pin "1") (pinfunction "1_1") (pintype "passive"))
      (node (ref "TP2") (pin "1") (pinfunction "Pad_1") (pintype "passive"))
    )
    (net (code "66") (name "/nRIGHT_PADDLE") (class "Default")
      (node (ref "R60") (pin "1") (pinfunction "1_1") (pintype "passive"))
      (node (ref "R62") (pin "1") (pinfunction "1_1") (pintype "passive"))
      (node (ref "TP3") (pin "1") (pinfunction "Pad_1") (pintype "passive"))
    )
    (net (code "67") (name "3V3") (class "Default")
      (node (ref "C14") (pin "1") (pinfunction "1_1") (pintype "passive"))
      (node (ref "C15") (pin "2") (pinfunction "2_2") (pintype "passive"))
      (node (ref "C2") (pin "1") (pinfunction "1_1") (pintype "passive"))
      (node (ref "C20") (pin "2") (pinfunction "2_2") (pintype "passive"))
      (node (ref "C3") (pin "2") (pinfunction "2_2") (pintype "passive"))
      (node (ref "C4") (pin "2") (pinfunction "2_2") (pintype "passive"))
      (node (ref "C5") (pin "2") (pinfunction "2_2") (pintype "passive"))
      (node (ref "C6") (pin "2") (pinfunction "2_2") (pintype "passive"))
      (node (ref "C7") (pin "2") (pinfunction "2_2") (pintype "passive"))
      (node (ref "D1") (pin "2") (pinfunction "A_2") (pintype "passive"))
      (node (ref "D1") (pin "3") (pinfunction "A_3") (pintype "passive"))
      (node (ref "D2") (pin "2") (pinfunction "A_2") (pintype "passive"))
      (node (ref "D2") (pin "3") (pinfunction "A_3") (pintype "passive"))
      (node (ref "FB1") (pin "1") (pinfunction "1_1") (pintype "passive"))
      (node (ref "J4") (pin "01") (pinfunction "01_01") (pintype "passive"))
      (node (ref "R13") (pin "1") (pinfunction "1_1") (pintype "passive"))
      (node (ref "R3") (pin "2") (pinfunction "2_2") (pintype "passive"))
      (node (ref "R5") (pin "1") (pinfunction "1_1") (pintype "passive"))
      (node (ref "R54") (pin "2") (pinfunction "2_2") (pintype "passive"))
      (node (ref "R59") (pin "2") (pinfunction "2_2") (pintype "passive"))
      (node (ref "SW1") (pin "2") (pinfunction "2_2") (pintype "passive"))
      (node (ref "U1") (pin "100") (pinfunction "VDD_100") (pintype "power_in"))
      (node (ref "U1") (pin "11") (pinfunction "VDD_11") (pintype "power_in"))
      (node (ref "U1") (pin "27") (pinfunction "VDD_27") (pintype "power_in"))
      (node (ref "U1") (pin "50") (pinfunction "VDD_50") (pintype "power_in"))
      (node (ref "U1") (pin "6") (pinfunction "VBAT_6") (pintype "power_in"))
      (node (ref "U1") (pin "75") (pinfunction "VDD_75") (pintype "power_in"))
    )
    (net (code "68") (name "GND") (class "Default")
      (node (ref "C1") (pin "2") (pinfunction "2_2") (pintype "passive"))
      (node (ref "C10") (pin "1") (pinfunction "1_1") (pintype "passive"))
      (node (ref "C11") (pin "1") (pinfunction "1_1") (pintype "passive"))
      (node (ref "C12") (pin "1") (pinfunction "1_1") (pintype "passive"))
      (node (ref "C13") (pin "1") (pinfunction "1_1") (pintype "passive"))
      (node (ref "C14") (pin "2") (pinfunction "2_2") (pintype "passive"))
      (node (ref "C15") (pin "1") (pinfunction "1_1") (pintype "passive"))
      (node (ref "C16") (pin "2") (pinfunction "2_2") (pintype "passive"))
      (node (ref "C17") (pin "1") (pinfunction "1_1") (pintype "passive"))
      (node (ref "C18") (pin "1") (pinfunction "1_1") (pintype "passive"))
      (node (ref "C19") (pin "1") (pinfunction "1_1") (pintype "passive"))
      (node (ref "C2") (pin "2") (pinfunction "2_2") (pintype "passive"))
      (node (ref "C21") (pin "2") (pinfunction "2_2") (pintype "passive"))
      (node (ref "C22") (pin "2") (pinfunction "2_2") (pintype "passive"))
      (node (ref "C23") (pin "2") (pinfunction "2_2") (pintype "passive"))
      (node (ref "C3") (pin "1") (pinfunction "1_1") (pintype "passive"))
      (node (ref "C4") (pin "1") (pinfunction "1_1") (pintype "passive"))
      (node (ref "C5") (pin "1") (pinfunction "1_1") (pintype "passive"))
      (node (ref "C6") (pin "1") (pinfunction "1_1") (pintype "passive"))
      (node (ref "C7") (pin "1") (pinfunction "1_1") (pintype "passive"))
      (node (ref "C8") (pin "2") (pinfunction "2_2") (pintype "passive"))
      (node (ref "C9") (pin "1") (pinfunction "1_1") (pintype "passive"))
      (node (ref "J4") (pin "03") (pinfunction "03_03") (pintype "passive"))
      (node (ref "J4") (pin "05") (pinfunction "05_05") (pintype "passive"))
      (node (ref "R11") (pin "1") (pinfunction "1_1") (pintype "passive"))
      (node (ref "R12") (pin "1") (pinfunction "1_1") (pintype "passive"))
      (node (ref "R53") (pin "1") (pinfunction "1_1") (pintype "passive"))
      (node (ref "R58") (pin "1") (pinfunction "1_1") (pintype "passive"))
      (node (ref "R63") (pin "1") (pinfunction "1_1") (pintype "passive"))
      (node (ref "SW2") (pin "2") (pinfunction "2_2") (pintype "passive"))
      (node (ref "U1") (pin "10") (pinfunction "VSS_10") (pintype "power_in"))
      (node (ref "U1") (pin "19") (pinfunction "VSSA_19") (pintype "power_in"))
      (node (ref "U1") (pin "26") (pinfunction "VSS_26") (pintype "power_in"))
      (node (ref "U1") (pin "49") (pinfunction "VSS_49") (pintype "power_in"))
      (node (ref "U1") (pin "74") (pinfunction "VSS_74") (pintype "power_in"))
      (node (ref "U1") (pin "99") (pinfunction "VSS_99") (pintype "power_in"))
      (node (ref "Y1") (pin "2") (pinfunction "GND_2") (pintype "power_in"))
      (node (ref "Y1") (pin "4") (pinfunction "GND_4") (pintype "power_in"))
    )
    (net (code "69") (name "Net-(C10-Pad2)") (class "Default")
      (node (ref "C10") (pin "2") (pinfunction "2_2") (pintype "passive"))
      (node (ref "C11") (pin "2") (pinfunction "2_2") (pintype "passive"))
      (node (ref "U1") (pin "48") (pinfunction "VCAP_48") (pintype "power_in"))
    )
    (net (code "70") (name "Net-(C12-Pad2)") (class "Default")
      (node (ref "C12") (pin "2") (pinfunction "2_2") (pintype "passive"))
      (node (ref "C13") (pin "2") (pinfunction "2_2") (pintype "passive"))
      (node (ref "U1") (pin "73") (pinfunction "VCAP_73") (pintype "power_in"))
    )
    (net (code "71") (name "Net-(D1-K-Pad1)") (class "Default")
      (node (ref "D1") (pin "1") (pinfunction "K_1") (pintype "passive"))
      (node (ref "R7") (pin "2") (pinfunction "2_2") (pintype "passive"))
    )
    (net (code "72") (name "Net-(D1-K-Pad4)") (class "Default")
      (node (ref "D1") (pin "4") (pinfunction "K_4") (pintype "passive"))
      (node (ref "R8") (pin "2") (pinfunction "2_2") (pintype "passive"))
    )
    (net (code "73") (name "Net-(D2-K-Pad1)") (class "Default")
      (node (ref "D2") (pin "1") (pinfunction "K_1") (pintype "passive"))
      (node (ref "R11") (pin "2") (pinfunction "2_2") (pintype "passive"))
    )
    (net (code "74") (name "Net-(D2-K-Pad4)") (class "Default")
      (node (ref "D2") (pin "4") (pinfunction "K_4") (pintype "passive"))
      (node (ref "R14") (pin "2") (pinfunction "2_2") (pintype "passive"))
    )
    (net (code "75") (name "Net-(R3-Pad1)") (class "Default")
      (node (ref "R3") (pin "1") (pinfunction "1_1") (pintype "passive"))
      (node (ref "R4") (pin "2") (pinfunction "2_2") (pintype "passive"))
      (node (ref "R6") (pin "1") (pinfunction "1_1") (pintype "passive"))
    )
    (net (code "76") (name "Net-(R9-Pad2)") (class "Default")
      (node (ref "R9") (pin "2") (pinfunction "2_2") (pintype "passive"))
      (node (ref "SW1") (pin "1") (pinfunction "1_1") (pintype "passive"))
    )
    (net (code "77") (name "Net-(R10-Pad2)") (class "Default")
      (node (ref "R10") (pin "2") (pinfunction "2_2") (pintype "passive"))
      (node (ref "SW2") (pin "1") (pinfunction "1_1") (pintype "passive"))
    )
    (net (code "78") (name "Net-(R54-Pad1)") (class "Default")
      (node (ref "R54") (pin "1") (pinfunction "1_1") (pintype "passive"))
      (node (ref "R55") (pin "2") (pinfunction "2_2") (pintype "passive"))
      (node (ref "R56") (pin "1") (pinfunction "1_1") (pintype "passive"))
    )
    (net (code "79") (name "Net-(R59-Pad1)") (class "Default")
      (node (ref "R59") (pin "1") (pinfunction "1_1") (pintype "passive"))
      (node (ref "R60") (pin "2") (pinfunction "2_2") (pintype "passive"))
      (node (ref "R61") (pin "1") (pinfunction "1_1") (pintype "passive"))
    )
    (net (code "80") (name "unconnected-(J4-Pad07)") (class "Default")
      (node (ref "J4") (pin "07") (pinfunction "07_07") (pintype "passive+no_connect"))
    )
    (net (code "81") (name "unconnected-(J4-Pad08)") (class "Default")
      (node (ref "J4") (pin "08") (pinfunction "08_08") (pintype "passive+no_connect"))
    )
    (net (code "82") (name "unconnected-(J4-Pad09)") (class "Default")
      (node (ref "J4") (pin "09") (pinfunction "09_09") (pintype "passive+no_connect"))
    )
    (net (code "83") (name "unconnected-(U1B-PA3-Pad25)") (class "Default")
      (node (ref "U1") (pin "25") (pinfunction "PA3_25") (pintype "bidirectional"))
    )
    (net (code "84") (name "unconnected-(U1B-PA4-Pad28)") (class "Default")
      (node (ref "U1") (pin "28") (pinfunction "PA4_28") (pintype "bidirectional"))
    )
    (net (code "85") (name "unconnected-(U1B-PA15-Pad77)") (class "Default")
      (node (ref "U1") (pin "77") (pinfunction "PA15_77") (pintype "bidirectional"))
    )
    (net (code "86") (name "unconnected-(U1B-PB4-Pad90)") (class "Default")
      (node (ref "U1") (pin "90") (pinfunction "PB4_90") (pintype "bidirectional"))
    )
    (net (code "87") (name "unconnected-(U1B-PB5-Pad91)") (class "Default")
      (node (ref "U1") (pin "91") (pinfunction "PB5_91") (pintype "bidirectional"))
    )
    (net (code "88") (name "unconnected-(U1B-PB9-Pad96)") (class "Default")
      (node (ref "U1") (pin "96") (pinfunction "PB9_96") (pintype "bidirectional"))
    )
    (net (code "89") (name "unconnected-(U1B-PC0-Pad15)") (class "Default")
      (node (ref "U1") (pin "15") (pinfunction "PC0_15") (pintype "bidirectional"))
    )
    (net (code "90") (name "unconnected-(U1B-PC1-Pad16)") (class "Default")
      (node (ref "U1") (pin "16") (pinfunction "PC1_16") (pintype "bidirectional"))
    )
    (net (code "91") (name "unconnected-(U1B-PC2_C-Pad17)") (class "Default")
      (node (ref "U1") (pin "17") (pinfunction "PC2_C_17") (pintype "bidirectional"))
    )
    (net (code "92") (name "unconnected-(U1B-PC3_C-Pad18)") (class "Default")
      (node (ref "U1") (pin "18") (pinfunction "PC3_C_18") (pintype "bidirectional"))
    )
    (net (code "93") (name "unconnected-(U1B-PC10-Pad78)") (class "Default")
      (node (ref "U1") (pin "78") (pinfunction "PC10_78") (pintype "bidirectional"))
    )
    (net (code "94") (name "unconnected-(U1B-PC11-Pad79)") (class "Default")
      (node (ref "U1") (pin "79") (pinfunction "PC11_79") (pintype "bidirectional"))
    )
    (net (code "95") (name "unconnected-(U1B-PC12-Pad80)") (class "Default")
      (node (ref "U1") (pin "80") (pinfunction "PC12_80") (pintype "bidirectional"))
    )
    (net (code "96") (name "unconnected-(U1B-PC13-Pad7)") (class "Default")
      (node (ref "U1") (pin "7") (pinfunction "PC13_7") (pintype "bidirectional"))
    )
    (net (code "97") (name "unconnected-(U1B-PD8-Pad55)") (class "Default")
      (node (ref "U1") (pin "55") (pinfunction "PD8_55") (pintype "bidirectional"))
    )
    (net (code "98") (name "unconnected-(U1B-PE0-Pad97)") (class "Default")
      (node (ref "U1") (pin "97") (pinfunction "PE0_97") (pintype "bidirectional"))
    )
    (net (code "99") (name "unconnected-(U1B-PE1-Pad98)") (class "Default")
      (node (ref "U1") (pin "98") (pinfunction "PE1_98") (pintype "bidirectional"))
    )
    (net (code "100") (name "unconnected-(U1B-PE2-Pad1)") (class "Default")
      (node (ref "U1") (pin "1") (pinfunction "PE2_1") (pintype "bidirectional"))
    )
    (net (code "101") (name "unconnected-(U1B-PE3-Pad2)") (class "Default")
      (node (ref "U1") (pin "2") (pinfunction "PE3_2") (pintype "bidirectional"))
    )
    (net (code "102") (name "unconnected-(U1B-PE4-Pad3)") (class "Default")
      (node (ref "U1") (pin "3") (pinfunction "PE4_3") (pintype "bidirectional"))
    )
    (net (code "103") (name "unconnected-(U1B-PE5-Pad4)") (class "Default")
      (node (ref "U1") (pin "4") (pinfunction "PE5_4") (pintype "bidirectional"))
    )
    (net (code "104") (name "unconnected-(U1B-PE6-Pad5)") (class "Default")
      (node (ref "U1") (pin "5") (pinfunction "PE6_5") (pintype "bidirectional"))
    )
  )
)
